# buslamp-r4_reverse.net
KiCad netlist of a schematic drawn in EAGLE
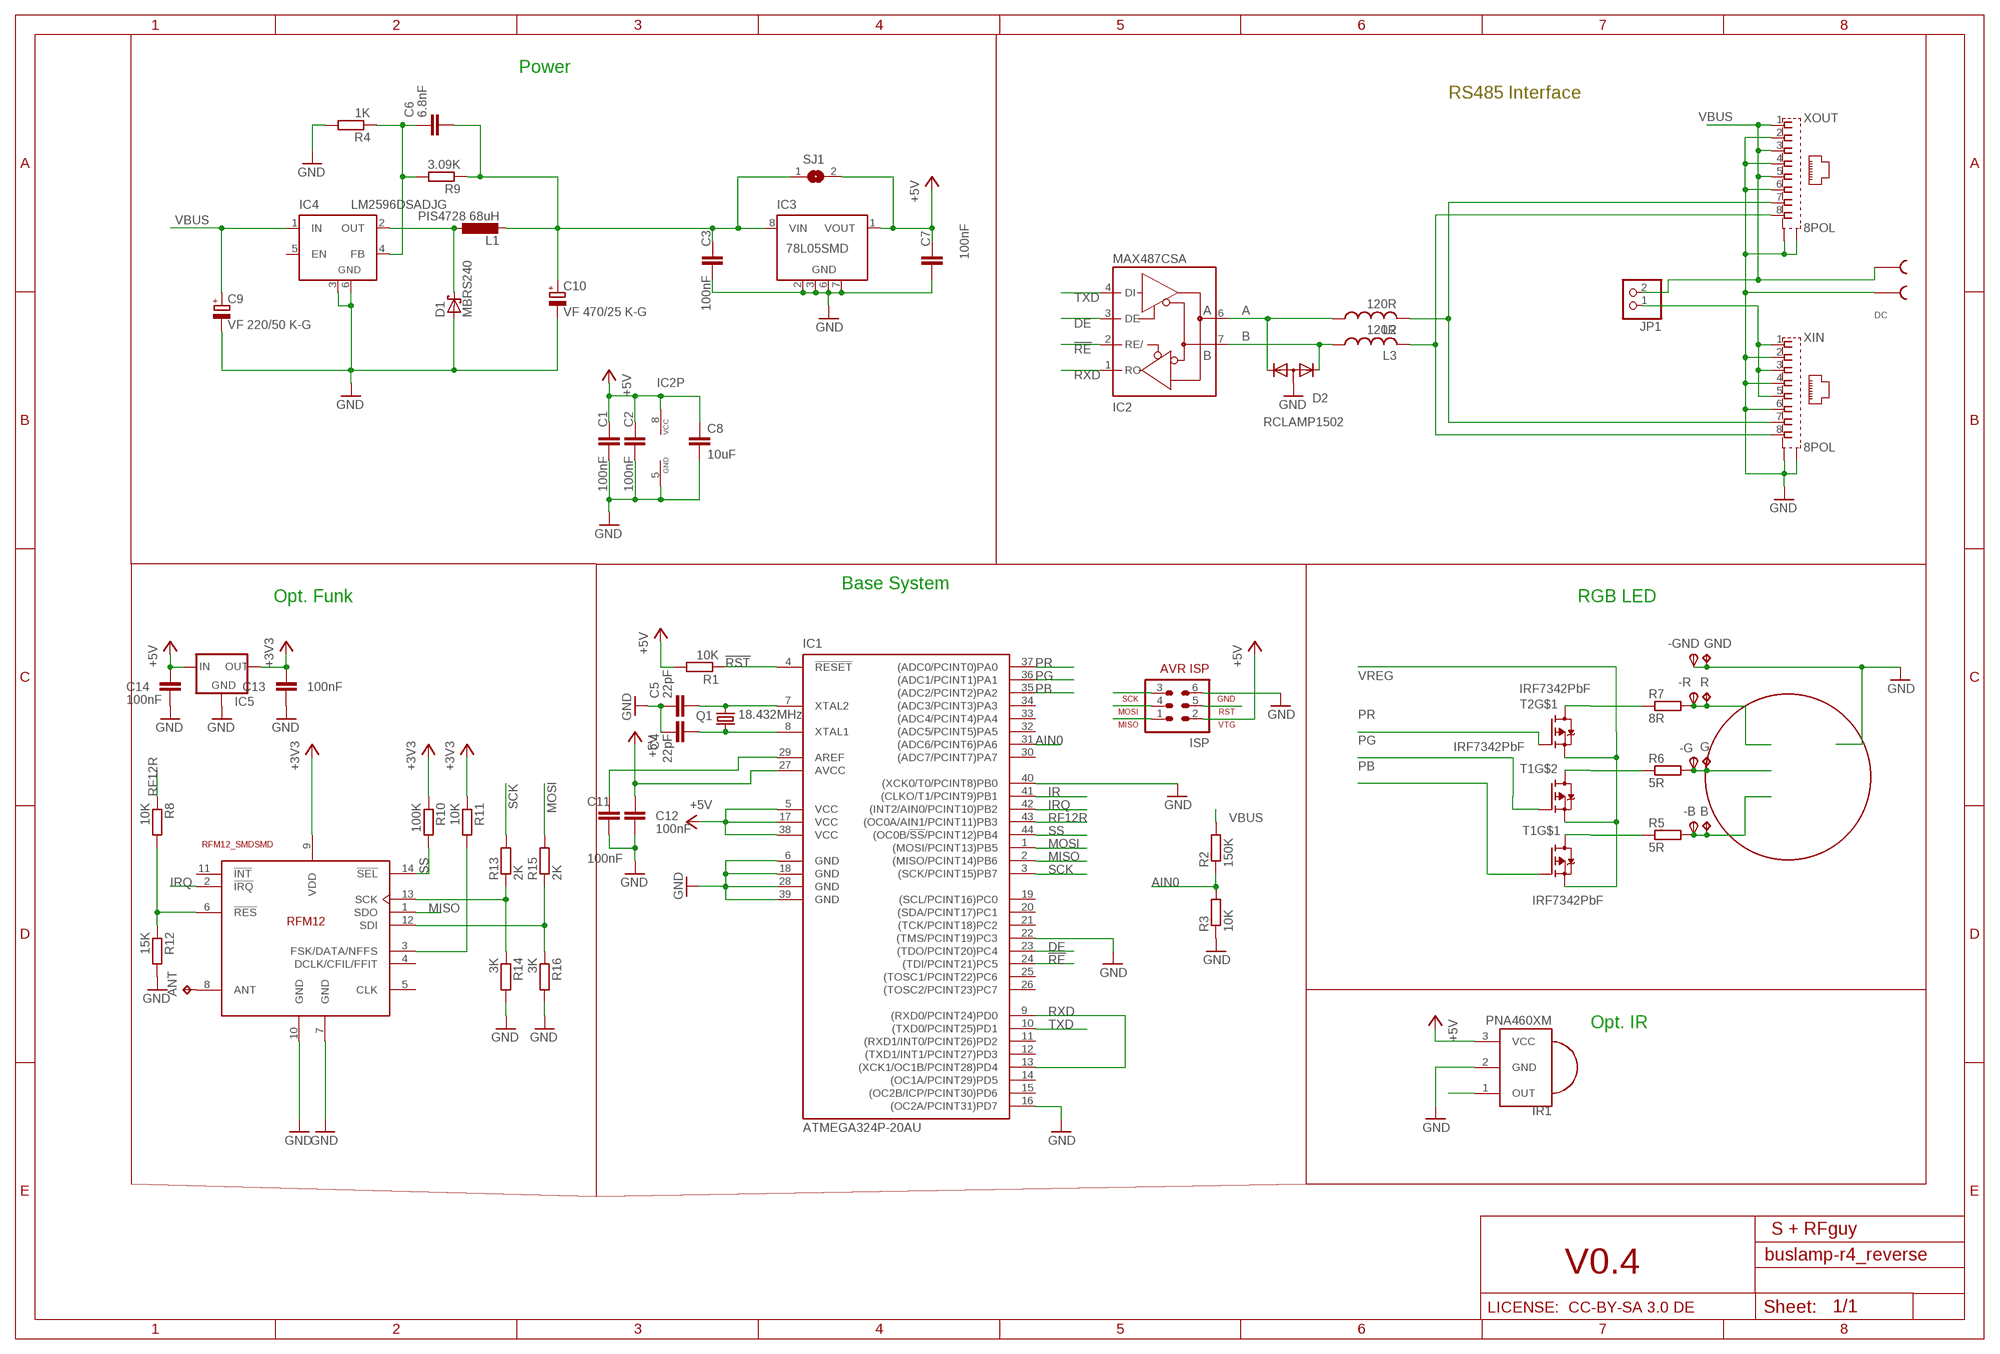
[diagram p0: schematic, sheet 1]

(export (version "E")
  (design (tool "Eeschema 10.0.6"))
  (components
    (comp (ref "-B")
      (value "TPSTP212R")
      (footprint "eagle-import:TP212R")
      (libsource (lib "eagle-import") (part "TPSTP212R"))
    )
    (comp (ref "-G")
      (value "TPSTP212R")
      (footprint "eagle-import:TP212R")
      (libsource (lib "eagle-import") (part "TPSTP212R"))
    )
    (comp (ref "-GND")
      (value "TPSTP212R")
      (footprint "eagle-import:TP212R")
      (libsource (lib "eagle-import") (part "TPSTP212R"))
    )
    (comp (ref "-R")
      (value "TPSTP212R")
      (footprint "eagle-import:TP212R")
      (libsource (lib "eagle-import") (part "TPSTP212R"))
    )
    (comp (ref "ANT")
      (value "TPPAD1-13")
      (footprint "eagle-import:P1-13")
      (libsource (lib "eagle-import") (part "TPPAD1-13"))
    )
    (comp (ref "B")
      (value "TPPAD1-13")
      (footprint "eagle-import:P1-13")
      (libsource (lib "eagle-import") (part "TPPAD1-13"))
    )
    (comp (ref "C1")
      (value "100nF")
      (footprint "eagle-import:C0805K")
      (libsource (lib "eagle-import") (part "C-EUC0805K"))
    )
    (comp (ref "C2")
      (value "100nF")
      (footprint "eagle-import:C0805K")
      (libsource (lib "eagle-import") (part "C-EUC0805K"))
    )
    (comp (ref "C3")
      (value "100nF")
      (footprint "eagle-import:C0805K")
      (libsource (lib "eagle-import") (part "C-EUC0805K"))
    )
    (comp (ref "C4")
      (value "22pF")
      (footprint "eagle-import:C0805K")
      (libsource (lib "eagle-import") (part "C-EUC0805K"))
    )
    (comp (ref "C5")
      (value "22pF")
      (footprint "eagle-import:C0805K")
      (libsource (lib "eagle-import") (part "C-EUC0805K"))
    )
    (comp (ref "C6")
      (value "6.8nF")
      (footprint "eagle-import:C0805K")
      (libsource (lib "eagle-import") (part "C-EUC0805K"))
    )
    (comp (ref "C7")
      (value "100nF")
      (footprint "eagle-import:C0805K")
      (libsource (lib "eagle-import") (part "C-EUC0805K"))
    )
    (comp (ref "C8")
      (value "10uF")
      (footprint "eagle-import:C1210")
      (libsource (lib "eagle-import") (part "C-EUC1210"))
    )
    (comp (ref "C9")
      (value "VF 220/50 K-G")
      (footprint "eagle-import:UD-10X10_NICHICON")
      (libsource (lib "eagle-import") (part "CPOL-EUUD-10X10"))
    )
    (comp (ref "C10")
      (value "VF 470/25 K-G")
      (footprint "eagle-import:UD-10X10_NICHICON")
      (libsource (lib "eagle-import") (part "CPOL-EUUD-10X10"))
    )
    (comp (ref "C11")
      (value "100nF")
      (footprint "eagle-import:C0805")
      (libsource (lib "eagle-import") (part "C-EUC0805"))
    )
    (comp (ref "C12")
      (value "100nF")
      (footprint "eagle-import:C0805")
      (libsource (lib "eagle-import") (part "C-EUC0805"))
    )
    (comp (ref "C13")
      (value "100nF")
      (footprint "eagle-import:C0805")
      (libsource (lib "eagle-import") (part "C-EUC0805"))
    )
    (comp (ref "C14")
      (value "100nF")
      (footprint "eagle-import:C0805")
      (libsource (lib "eagle-import") (part "C-EUC0805"))
    )
    (comp (ref "D1")
      (value "MBRS240")
      (footprint "eagle-import:SMB")
      (libsource (lib "eagle-import") (part "MBRS130LT3"))
    )
    (comp (ref "D2")
      (value "RCLAMP1502")
      (footprint "eagle-import:SOT23")
      (libsource (lib "eagle-import") (part "DIODE-2CA|ACSOT23"))
    )
    (comp (ref "DC")
      (value "STL-266-2")
      (footprint "eagle-import:STL-266-2")
      (libsource (lib "eagle-import") (part "STL-266-2"))
    )
    (comp (ref "G")
      (value "TPPAD1-13")
      (footprint "eagle-import:P1-13")
      (libsource (lib "eagle-import") (part "TPPAD1-13"))
    )
    (comp (ref "GND")
      (value "TPPAD1-13")
      (footprint "eagle-import:P1-13")
      (libsource (lib "eagle-import") (part "TPPAD1-13"))
    )
    (comp (ref "IC1")
      (value "ATMEGA324P-20AU")
      (footprint "eagle-import:TQFP44")
      (libsource (lib "eagle-import") (part "MEGA164P/324P/644P-AU"))
    )
    (comp (ref "IC2")
      (value "MAX487CSA")
      (footprint "eagle-import:SO08")
      (libsource (lib "eagle-import") (part "MAX481CSA"))
    )
    (comp (ref "IC3")
      (value "78L05SMD")
      (footprint "eagle-import:SO08")
      (libsource (lib "eagle-import") (part "78LSMD05"))
    )
    (comp (ref "IC4")
      (value "LM2596DSADJG")
      (footprint "eagle-import:TO263-5")
      (libsource (lib "eagle-import") (part "LM2596S"))
    )
    (comp (ref "IC5")
      (value "MCP1700SOT23")
      (footprint "eagle-import:SOT23")
      (libsource (lib "eagle-import") (part "MCP1700SOT23"))
    )
    (comp (ref "IR1")
      (value "PNA460XM")
      (footprint "eagle-import:PNA460XM")
      (libsource (lib "eagle-import") (part "PNA460XM"))
    )
    (comp (ref "ISP")
      (value "AVR-ISP-6")
      (footprint "eagle-import:AVR-ISP-6")
      (libsource (lib "eagle-import") (part "AVR-ISP-6"))
    )
    (comp (ref "JP1")
      (value "PINHD-1X2")
      (footprint "eagle-import:1X02")
      (libsource (lib "eagle-import") (part "PINHD-1X2"))
    )
    (comp (ref "L1")
      (value "PIS4728 68uH")
      (footprint "eagle-import:PIS4728")
      (libsource (lib "eagle-import") (part "PSI4728"))
    )
    (comp (ref "L2")
      (value "120R")
      (footprint "eagle-import:L0603")
      (libsource (lib "eagle-import") (part "L-USL0603"))
    )
    (comp (ref "L3")
      (value "120R")
      (footprint "eagle-import:L0603")
      (libsource (lib "eagle-import") (part "L-USL0603"))
    )
    (comp (ref "Q1")
      (value "18.432MHz")
      (footprint "eagle-import:HC49_S")
      (libsource (lib "eagle-import") (part "CRYTALHC49S"))
    )
    (comp (ref "R")
      (value "TPPAD1-13")
      (footprint "eagle-import:P1-13")
      (libsource (lib "eagle-import") (part "TPPAD1-13"))
    )
    (comp (ref "R1")
      (value "10K")
      (footprint "eagle-import:M0805")
      (libsource (lib "eagle-import") (part "R-EU_M0805"))
    )
    (comp (ref "R2")
      (value "150K")
      (footprint "eagle-import:R0805")
      (libsource (lib "eagle-import") (part "R-EU_R0805"))
    )
    (comp (ref "R3")
      (value "10K")
      (footprint "eagle-import:R0805")
      (libsource (lib "eagle-import") (part "R-EU_R0805"))
    )
    (comp (ref "R4")
      (value "1K")
      (footprint "eagle-import:M0805")
      (libsource (lib "eagle-import") (part "R-EU_M0805"))
    )
    (comp (ref "R5")
      (value "5R")
      (footprint "eagle-import:0617_17")
      (libsource (lib "eagle-import") (part "rclml_R-EU_0617/17"))
    )
    (comp (ref "R6")
      (value "5R")
      (footprint "eagle-import:0617_17")
      (libsource (lib "eagle-import") (part "rclml_R-EU_0617/17"))
    )
    (comp (ref "R7")
      (value "8R")
      (footprint "eagle-import:0617_17")
      (libsource (lib "eagle-import") (part "rclml_R-EU_0617/17"))
    )
    (comp (ref "R8")
      (value "10K")
      (footprint "eagle-import:M0805")
      (libsource (lib "eagle-import") (part "R-EU_M0805"))
    )
    (comp (ref "R9")
      (value "3.09K")
      (footprint "eagle-import:M0805")
      (libsource (lib "eagle-import") (part "R-EU_M0805"))
    )
    (comp (ref "R10")
      (value "100K")
      (footprint "eagle-import:M0805")
      (libsource (lib "eagle-import") (part "R-EU_M0805"))
    )
    (comp (ref "R11")
      (value "10K")
      (footprint "eagle-import:M0805")
      (libsource (lib "eagle-import") (part "R-EU_M0805"))
    )
    (comp (ref "R12")
      (value "15K")
      (footprint "eagle-import:M0805")
      (libsource (lib "eagle-import") (part "R-EU_M0805"))
    )
    (comp (ref "R13")
      (value "2K")
      (footprint "eagle-import:M0805")
      (libsource (lib "eagle-import") (part "R-EU_M0805"))
    )
    (comp (ref "R14")
      (value "3K")
      (footprint "eagle-import:M0805")
      (libsource (lib "eagle-import") (part "R-EU_M0805"))
    )
    (comp (ref "R15")
      (value "2K")
      (footprint "eagle-import:M0805")
      (libsource (lib "eagle-import") (part "R-EU_M0805"))
    )
    (comp (ref "R16")
      (value "3K")
      (footprint "eagle-import:M0805")
      (libsource (lib "eagle-import") (part "R-EU_M0805"))
    )
    (comp (ref "RF1")
      (value "RFM12_SMDSMD")
      (footprint "eagle-import:RFM12")
      (libsource (lib "eagle-import") (part "RFM12_SMDSMD"))
    )
    (comp (ref "SJ1") (value "SJ") (footprint "eagle-import:SJ") (libsource (lib "eagle-import") (part "SJ")))
    (comp (ref "T1")
      (value "IRF7342PbF")
      (footprint "eagle-import:SO08-IRF")
      (libsource (lib "eagle-import") (part "IRF7342PBF"))
    )
    (comp (ref "T2")
      (value "IRF7342PbF")
      (footprint "eagle-import:SO08-IRF")
      (libsource (lib "eagle-import") (part "IRF7342PBF"))
    )
    (comp (ref "U$2")
      (value "KK-STERN")
      (footprint "eagle-import:STERN")
      (libsource (lib "eagle-import") (part "KK-STERN"))
    )
    (comp (ref "XIN")
      (value "8POL")
      (footprint "eagle-import:8POL")
      (libsource (lib "eagle-import") (part "8POL"))
    )
    (comp (ref "XOUT")
      (value "8POL")
      (footprint "eagle-import:8POL")
      (libsource (lib "eagle-import") (part "8POL"))
    )
  )
  (nets
    (net (code "1") (name "+3V3") (class "Default")
      (node (ref "C13") (pin "2") (pinfunction "2_2") (pintype "passive"))
      (node (ref "IC5") (pin "2") (pinfunction "OUT_2") (pintype "passive"))
      (node (ref "R10") (pin "1") (pinfunction "1_1") (pintype "passive"))
      (node (ref "R11") (pin "1") (pinfunction "1_1") (pintype "passive"))
      (node (ref "RF1") (pin "9") (pinfunction "VDD_9") (pintype "power_in"))
    )
    (net (code "2") (name "+5V") (class "Default")
      (node (ref "C1") (pin "1") (pinfunction "1_1") (pintype "passive"))
      (node (ref "C12") (pin "2") (pinfunction "2_2") (pintype "passive"))
      (node (ref "C14") (pin "2") (pinfunction "2_2") (pintype "passive"))
      (node (ref "C2") (pin "1") (pinfunction "1_1") (pintype "passive"))
      (node (ref "C7") (pin "1") (pinfunction "1_1") (pintype "passive"))
      (node (ref "C8") (pin "1") (pinfunction "1_1") (pintype "passive"))
      (node (ref "IC1") (pin "17") (pinfunction "VCC_17") (pintype "power_in"))
      (node (ref "IC1") (pin "27") (pinfunction "AVCC_27") (pintype "power_in"))
      (node (ref "IC1") (pin "38") (pinfunction "VCC_38") (pintype "power_in"))
      (node (ref "IC1") (pin "5") (pinfunction "VCC_5") (pintype "power_in"))
      (node (ref "IC2") (pin "8") (pinfunction "VCC_8") (pintype "power_in"))
      (node (ref "IC3") (pin "1") (pinfunction "VOUT_1") (pintype "output"))
      (node (ref "IC5") (pin "3") (pinfunction "IN_3") (pintype "input"))
      (node (ref "IR1") (pin "3") (pinfunction "VCC_3") (pintype "power_in"))
      (node (ref "ISP") (pin "2") (pinfunction "2_2") (pintype "passive"))
      (node (ref "R1") (pin "2") (pinfunction "2_2") (pintype "passive"))
      (node (ref "SJ1") (pin "2") (pinfunction "2_2") (pintype "passive"))
    )
    (net (code "3") (name "/A") (class "Default")
      (node (ref "L2") (pin "2") (pinfunction "2_2") (pintype "passive"))
      (node (ref "XIN") (pin "7") (pinfunction "7_7") (pintype "passive"))
      (node (ref "XOUT") (pin "7") (pinfunction "7_7") (pintype "passive"))
    )
    (net (code "4") (name "/AIN0") (class "Default")
      (node (ref "IC1") (pin "31") (pinfunction "(ADC6/PCINT6)PA6_31") (pintype "bidirectional"))
      (node (ref "R2") (pin "1") (pinfunction "1_1") (pintype "passive"))
      (node (ref "R3") (pin "2") (pinfunction "2_2") (pintype "passive"))
    )
    (net (code "5") (name "/B") (class "Default")
      (node (ref "L3") (pin "2") (pinfunction "2_2") (pintype "passive"))
      (node (ref "XIN") (pin "8") (pinfunction "8_8") (pintype "passive"))
      (node (ref "XOUT") (pin "8") (pinfunction "8_8") (pintype "passive"))
    )
    (net (code "6") (name "/DE") (class "Default")
      (node (ref "IC1") (pin "23") (pinfunction "(TDO/PCINT20)PC4_23") (pintype "bidirectional"))
      (node (ref "IC2") (pin "3") (pinfunction "DE_3") (pintype "input"))
    )
    (net (code "7") (name "/IR") (class "Default")
      (node (ref "IC1") (pin "41") (pinfunction "(CLKO/T1/PCINT9)PB1_41") (pintype "bidirectional"))
      (node (ref "IR1") (pin "1") (pinfunction "OUT_1") (pintype "output"))
    )
    (net (code "8") (name "/IRQ") (class "Default")
      (node (ref "IC1") (pin "42") (pinfunction "(INT2/AIN0/PCINT10)PB2_42") (pintype "bidirectional"))
      (node (ref "RF1") (pin "2") (pinfunction "~{IRQ}_2") (pintype "output"))
    )
    (net (code "9") (name "/MISO") (class "Default")
      (node (ref "IC1") (pin "2") (pinfunction "(MISO/PCINT14)PB6_2") (pintype "bidirectional"))
      (node (ref "ISP") (pin "1") (pinfunction "1_1") (pintype "passive"))
      (node (ref "RF1") (pin "1") (pinfunction "SDO_1") (pintype "output"))
    )
    (net (code "10") (name "/MOSI") (class "Default")
      (node (ref "IC1") (pin "1") (pinfunction "(MOSI/PCINT13)PB5_1") (pintype "bidirectional"))
      (node (ref "ISP") (pin "4") (pinfunction "4_4") (pintype "passive"))
      (node (ref "R15") (pin "2") (pinfunction "2_2") (pintype "passive"))
    )
    (net (code "11") (name "/PB") (class "Default")
      (node (ref "IC1") (pin "35") (pinfunction "(ADC2/PCINT2)PA2_35") (pintype "bidirectional"))
      (node (ref "T1") (pin "2") (pinfunction "G_2") (pintype "passive"))
    )
    (net (code "12") (name "/PG") (class "Default")
      (node (ref "IC1") (pin "36") (pinfunction "(ADC1/PCINT1)PA1_36") (pintype "bidirectional"))
      (node (ref "T1") (pin "4") (pinfunction "G_4") (pintype "passive"))
    )
    (net (code "13") (name "/PR") (class "Default")
      (node (ref "IC1") (pin "37") (pinfunction "(ADC0/PCINT0)PA0_37") (pintype "bidirectional"))
      (node (ref "T2") (pin "2") (pinfunction "G_2") (pintype "passive"))
    )
    (net (code "14") (name "/RF12R") (class "Default")
      (node (ref "IC1") (pin "43") (pinfunction "(OC0A/AIN1/PCINT11)PB3_43") (pintype "bidirectional"))
      (node (ref "R8") (pin "1") (pinfunction "1_1") (pintype "passive"))
    )
    (net (code "15") (name "/RXD") (class "Default")
      (node (ref "IC1") (pin "13") (pinfunction "(XCK1/OC1B/PCINT28)PD4_13") (pintype "bidirectional"))
      (node (ref "IC1") (pin "9") (pinfunction "(RXD0/PCINT24)PD0_9") (pintype "bidirectional"))
      (node (ref "IC2") (pin "1") (pinfunction "RO_1") (pintype "output"))
    )
    (net (code "16") (name "/SCK") (class "Default")
      (node (ref "IC1") (pin "3") (pinfunction "(SCK/PCINT15)PB7_3") (pintype "bidirectional"))
      (node (ref "ISP") (pin "3") (pinfunction "3_3") (pintype "passive"))
      (node (ref "R13") (pin "2") (pinfunction "2_2") (pintype "passive"))
    )
    (net (code "17") (name "/SS") (class "Default")
      (node (ref "IC1") (pin "44") (pinfunction "(OC0B/~{SS}/PCINT12)PB4_44") (pintype "bidirectional"))
      (node (ref "R10") (pin "2") (pinfunction "2_2") (pintype "passive"))
      (node (ref "RF1") (pin "14") (pinfunction "~{SEL}_14") (pintype "input"))
    )
    (net (code "18") (name "/TXD") (class "Default")
      (node (ref "IC1") (pin "10") (pinfunction "(TXD0/PCINT25)PD1_10") (pintype "bidirectional"))
      (node (ref "IC2") (pin "4") (pinfunction "DI_4") (pintype "input"))
    )
    (net (code "19") (name "/VBUS") (class "Default")
      (node (ref "C9") (pin "+") (pinfunction "+_+") (pintype "passive"))
      (node (ref "DC") (pin "P$4") (pinfunction "P$2_P$4") (pintype "bidirectional"))
      (node (ref "IC4") (pin "1") (pinfunction "IN_1") (pintype "input"))
      (node (ref "JP1") (pin "2") (pinfunction "2_2") (pintype "passive"))
      (node (ref "R2") (pin "2") (pinfunction "2_2") (pintype "passive"))
      (node (ref "XOUT") (pin "1") (pinfunction "1_1") (pintype "passive"))
      (node (ref "XOUT") (pin "3") (pinfunction "3_3") (pintype "passive"))
      (node (ref "XOUT") (pin "5") (pinfunction "5_5") (pintype "passive"))
    )
    (net (code "20") (name "/VREG") (class "Default")
      (node (ref "C10") (pin "+") (pinfunction "+_+") (pintype "passive"))
      (node (ref "C3") (pin "1") (pinfunction "1_1") (pintype "passive"))
      (node (ref "C6") (pin "2") (pinfunction "2_2") (pintype "passive"))
      (node (ref "IC3") (pin "8") (pinfunction "VIN_8") (pintype "passive"))
      (node (ref "L1") (pin "2") (pinfunction "2_2") (pintype "passive"))
      (node (ref "R9") (pin "1") (pinfunction "1_1") (pintype "passive"))
      (node (ref "SJ1") (pin "1") (pinfunction "1_1") (pintype "passive"))
      (node (ref "T1") (pin "1") (pinfunction "S_1") (pintype "passive"))
      (node (ref "T1") (pin "3") (pinfunction "S_3") (pintype "passive"))
      (node (ref "T2") (pin "1") (pinfunction "S_1") (pintype "passive"))
    )
    (net (code "21") (name "/~{RE}") (class "Default")
      (node (ref "IC1") (pin "24") (pinfunction "(TDI/PCINT21)PC5_24") (pintype "bidirectional"))
      (node (ref "IC2") (pin "2") (pinfunction "RE/_2") (pintype "input"))
    )
    (net (code "22") (name "/~{RST}") (class "Default")
      (node (ref "IC1") (pin "4") (pinfunction "~{RESET}_4") (pintype "input"))
      (node (ref "ISP") (pin "5") (pinfunction "5_5") (pintype "passive"))
      (node (ref "R1") (pin "1") (pinfunction "1_1") (pintype "passive"))
    )
    (net (code "23") (name "GND") (class "Default")
      (node (ref "-GND") (pin "TP") (pinfunction "PP_TP") (pintype "input"))
      (node (ref "C1") (pin "2") (pinfunction "2_2") (pintype "passive"))
      (node (ref "C10") (pin "-") (pinfunction "-_-") (pintype "passive"))
      (node (ref "C11") (pin "1") (pinfunction "1_1") (pintype "passive"))
      (node (ref "C12") (pin "1") (pinfunction "1_1") (pintype "passive"))
      (node (ref "C13") (pin "1") (pinfunction "1_1") (pintype "passive"))
      (node (ref "C14") (pin "1") (pinfunction "1_1") (pintype "passive"))
      (node (ref "C2") (pin "2") (pinfunction "2_2") (pintype "passive"))
      (node (ref "C3") (pin "2") (pinfunction "2_2") (pintype "passive"))
      (node (ref "C4") (pin "1") (pinfunction "1_1") (pintype "passive"))
      (node (ref "C5") (pin "1") (pinfunction "1_1") (pintype "passive"))
      (node (ref "C7") (pin "2") (pinfunction "2_2") (pintype "passive"))
      (node (ref "C8") (pin "2") (pinfunction "2_2") (pintype "passive"))
      (node (ref "C9") (pin "-") (pinfunction "-_-") (pintype "passive"))
      (node (ref "D1") (pin "A") (pinfunction "A_A") (pintype "passive"))
      (node (ref "D2") (pin "3") (pinfunction "A_3") (pintype "passive"))
      (node (ref "DC") (pin "P$3") (pinfunction "P$1_P$3") (pintype "bidirectional"))
      (node (ref "GND") (pin "TP") (pinfunction "TP_TP") (pintype "input"))
      (node (ref "IC1") (pin "16") (pinfunction "(OC2A/PCINT31)PD7_16") (pintype "bidirectional"))
      (node (ref "IC1") (pin "18") (pinfunction "GND_18") (pintype "power_in"))
      (node (ref "IC1") (pin "22") (pinfunction "(TMS/PCINT19)PC3_22") (pintype "bidirectional"))
      (node (ref "IC1") (pin "28") (pinfunction "GND_28") (pintype "power_in"))
      (node (ref "IC1") (pin "39") (pinfunction "GND_39") (pintype "power_in"))
      (node (ref "IC1") (pin "40") (pinfunction "(XCK0/T0/PCINT8)PB0_40") (pintype "bidirectional"))
      (node (ref "IC1") (pin "6") (pinfunction "GND_6") (pintype "power_in"))
      (node (ref "IC2") (pin "5") (pinfunction "GND_5") (pintype "power_in"))
      (node (ref "IC3") (pin "2") (pinfunction "GND_2") (pintype "power_in"))
      (node (ref "IC3") (pin "3") (pinfunction "GND_3") (pintype "power_in"))
      (node (ref "IC3") (pin "6") (pinfunction "GND_6") (pintype "power_in"))
      (node (ref "IC3") (pin "7") (pinfunction "GND_7") (pintype "power_in"))
      (node (ref "IC4") (pin "3") (pinfunction "GND_3") (pintype "power_in"))
      (node (ref "IC4") (pin "6") (pinfunction "GND_6") (pintype "power_in"))
      (node (ref "IC5") (pin "1") (pinfunction "GND_1") (pintype "input"))
      (node (ref "IR1") (pin "2") (pinfunction "GND_2") (pintype "power_in"))
      (node (ref "ISP") (pin "6") (pinfunction "6_6") (pintype "passive"))
      (node (ref "R12") (pin "2") (pinfunction "2_2") (pintype "passive"))
      (node (ref "R14") (pin "2") (pinfunction "2_2") (pintype "passive"))
      (node (ref "R16") (pin "2") (pinfunction "2_2") (pintype "passive"))
      (node (ref "R3") (pin "1") (pinfunction "1_1") (pintype "passive"))
      (node (ref "R4") (pin "2") (pinfunction "2_2") (pintype "passive"))
      (node (ref "RF1") (pin "10") (pinfunction "GND_10") (pintype "passive"))
      (node (ref "RF1") (pin "7") (pinfunction "GND_7") (pintype "passive"))
      (node (ref "XIN") (pin "2") (pinfunction "2_2") (pintype "passive"))
      (node (ref "XIN") (pin "4") (pinfunction "4_4") (pintype "passive"))
      (node (ref "XIN") (pin "6") (pinfunction "6_6") (pintype "passive"))
      (node (ref "XIN") (pin "S1") (pinfunction "S1_S1") (pintype "passive"))
      (node (ref "XIN") (pin "S2") (pinfunction "S2_S2") (pintype "passive"))
      (node (ref "XOUT") (pin "2") (pinfunction "2_2") (pintype "passive"))
      (node (ref "XOUT") (pin "4") (pinfunction "4_4") (pintype "passive"))
      (node (ref "XOUT") (pin "6") (pinfunction "6_6") (pintype "passive"))
      (node (ref "XOUT") (pin "S1") (pinfunction "S1_S1") (pintype "passive"))
      (node (ref "XOUT") (pin "S2") (pinfunction "S2_S2") (pintype "passive"))
    )
    (net (code "24") (name "Net-(-B-PP)") (class "Default")
      (node (ref "-B") (pin "TP") (pinfunction "PP_TP") (pintype "input"))
      (node (ref "B") (pin "TP") (pinfunction "TP_TP") (pintype "input"))
      (node (ref "R5") (pin "2") (pinfunction "2_2") (pintype "passive"))
    )
    (net (code "25") (name "Net-(-G-PP)") (class "Default")
      (node (ref "-G") (pin "TP") (pinfunction "PP_TP") (pintype "input"))
      (node (ref "G") (pin "TP") (pinfunction "TP_TP") (pintype "input"))
      (node (ref "R6") (pin "2") (pinfunction "2_2") (pintype "passive"))
    )
    (net (code "26") (name "Net-(-R-PP)") (class "Default")
      (node (ref "-R") (pin "TP") (pinfunction "PP_TP") (pintype "input"))
      (node (ref "R") (pin "TP") (pinfunction "TP_TP") (pintype "input"))
      (node (ref "R7") (pin "2") (pinfunction "2_2") (pintype "passive"))
    )
    (net (code "27") (name "Net-(D2-K1)") (class "Default")
      (node (ref "D2") (pin "1") (pinfunction "K1_1") (pintype "passive"))
      (node (ref "IC2") (pin "7") (pinfunction "B_7") (pintype "passive"))
      (node (ref "L3") (pin "1") (pinfunction "1_1") (pintype "passive"))
    )
    (net (code "28") (name "Net-(D2-K2)") (class "Default")
      (node (ref "D2") (pin "2") (pinfunction "K2_2") (pintype "passive"))
      (node (ref "IC2") (pin "6") (pinfunction "A_6") (pintype "passive"))
      (node (ref "L2") (pin "1") (pinfunction "1_1") (pintype "passive"))
    )
    (net (code "29") (name "Net-(IC1-AREF)") (class "Default")
      (node (ref "C11") (pin "2") (pinfunction "2_2") (pintype "passive"))
      (node (ref "IC1") (pin "29") (pinfunction "AREF_29") (pintype "power_in"))
    )
    (net (code "30") (name "Net-(IC1-XTAL1)") (class "Default")
      (node (ref "C4") (pin "2") (pinfunction "2_2") (pintype "passive"))
      (node (ref "IC1") (pin "8") (pinfunction "XTAL1_8") (pintype "input"))
      (node (ref "Q1") (pin "1") (pinfunction "1_1") (pintype "passive"))
    )
    (net (code "31") (name "Net-(IC1-XTAL2)") (class "Default")
      (node (ref "C5") (pin "2") (pinfunction "2_2") (pintype "passive"))
      (node (ref "IC1") (pin "7") (pinfunction "XTAL2_7") (pintype "output"))
      (node (ref "Q1") (pin "2") (pinfunction "2_2") (pintype "passive"))
    )
    (net (code "32") (name "Net-(IC4-FB)") (class "Default")
      (node (ref "C6") (pin "1") (pinfunction "1_1") (pintype "passive"))
      (node (ref "IC4") (pin "4") (pinfunction "FB_4") (pintype "input"))
      (node (ref "R4") (pin "1") (pinfunction "1_1") (pintype "passive"))
      (node (ref "R9") (pin "2") (pinfunction "2_2") (pintype "passive"))
    )
    (net (code "33") (name "Net-(IC4-OUT)") (class "Default")
      (node (ref "D1") (pin "C") (pinfunction "C_C") (pintype "passive"))
      (node (ref "IC4") (pin "2") (pinfunction "OUT_2") (pintype "output"))
      (node (ref "L1") (pin "1") (pinfunction "1_1") (pintype "passive"))
    )
    (net (code "34") (name "Net-(JP1-Pad1)") (class "Default")
      (node (ref "JP1") (pin "1") (pinfunction "1_1") (pintype "passive"))
      (node (ref "XIN") (pin "1") (pinfunction "1_1") (pintype "passive"))
      (node (ref "XIN") (pin "3") (pinfunction "3_3") (pintype "passive"))
      (node (ref "XIN") (pin "5") (pinfunction "5_5") (pintype "passive"))
    )
    (net (code "35") (name "Net-(R5-Pad1)") (class "Default")
      (node (ref "R5") (pin "1") (pinfunction "1_1") (pintype "passive"))
      (node (ref "T1") (pin "7") (pinfunction "D_7") (pintype "passive"))
      (node (ref "T1") (pin "8") (pinfunction "D_8") (pintype "passive"))
    )
    (net (code "36") (name "Net-(R6-Pad1)") (class "Default")
      (node (ref "R6") (pin "1") (pinfunction "1_1") (pintype "passive"))
      (node (ref "T1") (pin "5") (pinfunction "D_5") (pintype "passive"))
      (node (ref "T1") (pin "6") (pinfunction "D_6") (pintype "passive"))
    )
    (net (code "37") (name "Net-(R7-Pad1)") (class "Default")
      (node (ref "R7") (pin "1") (pinfunction "1_1") (pintype "passive"))
      (node (ref "T2") (pin "7") (pinfunction "D_7") (pintype "passive"))
      (node (ref "T2") (pin "8") (pinfunction "D_8") (pintype "passive"))
    )
    (net (code "38") (name "Net-(RF1-ANT)") (class "Default")
      (node (ref "ANT") (pin "TP") (pinfunction "TP_TP") (pintype "input"))
      (node (ref "RF1") (pin "8") (pinfunction "ANT_8") (pintype "bidirectional"))
    )
    (net (code "39") (name "Net-(RF1-FSK{slash}DATA{slash}NFFS)") (class "Default")
      (node (ref "R11") (pin "2") (pinfunction "2_2") (pintype "passive"))
      (node (ref "RF1") (pin "3") (pinfunction "FSK/DATA/NFFS_3") (pintype "bidirectional"))
    )
    (net (code "40") (name "Net-(RF1-SCK)") (class "Default")
      (node (ref "R13") (pin "1") (pinfunction "1_1") (pintype "passive"))
      (node (ref "R14") (pin "1") (pinfunction "1_1") (pintype "passive"))
      (node (ref "RF1") (pin "13") (pinfunction "SCK_13") (pintype "input"))
    )
    (net (code "41") (name "Net-(RF1-SDI)") (class "Default")
      (node (ref "R15") (pin "1") (pinfunction "1_1") (pintype "passive"))
      (node (ref "R16") (pin "1") (pinfunction "1_1") (pintype "passive"))
      (node (ref "RF1") (pin "12") (pinfunction "SDI_12") (pintype "input"))
    )
    (net (code "42") (name "Net-(RF1-~{RES})") (class "Default")
      (node (ref "R12") (pin "1") (pinfunction "1_1") (pintype "passive"))
      (node (ref "R8") (pin "2") (pinfunction "2_2") (pintype "passive"))
      (node (ref "RF1") (pin "6") (pinfunction "~{RES}_6") (pintype "bidirectional"))
    )
    (net (code "43") (name "unconnected-(IC1-(ADC3{slash}PCINT3)PA3-Pad34)") (class "Default")
      (node (ref "IC1") (pin "34") (pinfunction "(ADC3/PCINT3)PA3_34") (pintype "bidirectional"))
    )
    (net (code "44") (name "unconnected-(IC1-(ADC4{slash}PCINT4)PA4-Pad33)") (class "Default")
      (node (ref "IC1") (pin "33") (pinfunction "(ADC4/PCINT4)PA4_33") (pintype "bidirectional"))
    )
    (net (code "45") (name "unconnected-(IC1-(ADC5{slash}PCINT5)PA5-Pad32)") (class "Default")
      (node (ref "IC1") (pin "32") (pinfunction "(ADC5/PCINT5)PA5_32") (pintype "bidirectional"))
    )
    (net (code "46") (name "unconnected-(IC1-(ADC7{slash}PCINT7)PA7-Pad30)") (class "Default")
      (node (ref "IC1") (pin "30") (pinfunction "(ADC7/PCINT7)PA7_30") (pintype "bidirectional"))
    )
    (net (code "47") (name "unconnected-(IC1-(OC1A{slash}PCINT29)PD5-Pad14)") (class "Default")
      (node (ref "IC1") (pin "14") (pinfunction "(OC1A/PCINT29)PD5_14") (pintype "bidirectional"))
    )
    (net (code "48") (name "unconnected-(IC1-(OC2B{slash}ICP{slash}PCINT30)PD6-Pad15)") (class "Default")
      (node (ref "IC1") (pin "15") (pinfunction "(OC2B/ICP/PCINT30)PD6_15") (pintype "bidirectional"))
    )
    (net (code "49") (name "unconnected-(IC1-(RXD1{slash}INT0{slash}PCINT26)PD2-Pad11)") (class "Default")
      (node (ref "IC1") (pin "11") (pinfunction "(RXD1/INT0/PCINT26)PD2_11") (pintype "bidirectional"))
    )
    (net (code "50") (name "unconnected-(IC1-(SCL{slash}PCINT16)PC0-Pad19)") (class "Default")
      (node (ref "IC1") (pin "19") (pinfunction "(SCL/PCINT16)PC0_19") (pintype "bidirectional"))
    )
    (net (code "51") (name "unconnected-(IC1-(SDA{slash}PCINT17)PC1-Pad20)") (class "Default")
      (node (ref "IC1") (pin "20") (pinfunction "(SDA/PCINT17)PC1_20") (pintype "bidirectional"))
    )
    (net (code "52") (name "unconnected-(IC1-(TCK{slash}PCINT18)PC2-Pad21)") (class "Default")
      (node (ref "IC1") (pin "21") (pinfunction "(TCK/PCINT18)PC2_21") (pintype "bidirectional"))
    )
    (net (code "53") (name "unconnected-(IC1-(TOSC1{slash}PCINT22)PC6-Pad25)") (class "Default")
      (node (ref "IC1") (pin "25") (pinfunction "(TOSC1/PCINT22)PC6_25") (pintype "bidirectional"))
    )
    (net (code "54") (name "unconnected-(IC1-(TOSC2{slash}PCINT23)PC7-Pad26)") (class "Default")
      (node (ref "IC1") (pin "26") (pinfunction "(TOSC2/PCINT23)PC7_26") (pintype "bidirectional"))
    )
    (net (code "55") (name "unconnected-(IC1-(TXD1{slash}INT1{slash}PCINT27)PD3-Pad12)") (class "Default")
      (node (ref "IC1") (pin "12") (pinfunction "(TXD1/INT1/PCINT27)PD3_12") (pintype "bidirectional"))
    )
    (net (code "56") (name "unconnected-(IC4-EN-Pad5)") (class "Default")
      (node (ref "IC4") (pin "5") (pinfunction "EN_5") (pintype "input"))
    )
    (net (code "57") (name "unconnected-(RF1-CLK-Pad5)") (class "Default")
      (node (ref "RF1") (pin "5") (pinfunction "CLK_5") (pintype "output"))
    )
    (net (code "58") (name "unconnected-(RF1-DCLK{slash}CFIL{slash}FFIT-Pad4)") (class "Default")
      (node (ref "RF1") (pin "4") (pinfunction "DCLK/CFIL/FFIT_4") (pintype "bidirectional"))
    )
    (net (code "59") (name "unconnected-(RF1-~{INT}-Pad11)") (class "Default")
      (node (ref "RF1") (pin "11") (pinfunction "~{INT}_11") (pintype "bidirectional"))
    )
  )
)
